# motor_driver_ver3_6.net
KiCad netlist of a schematic drawn in EAGLE
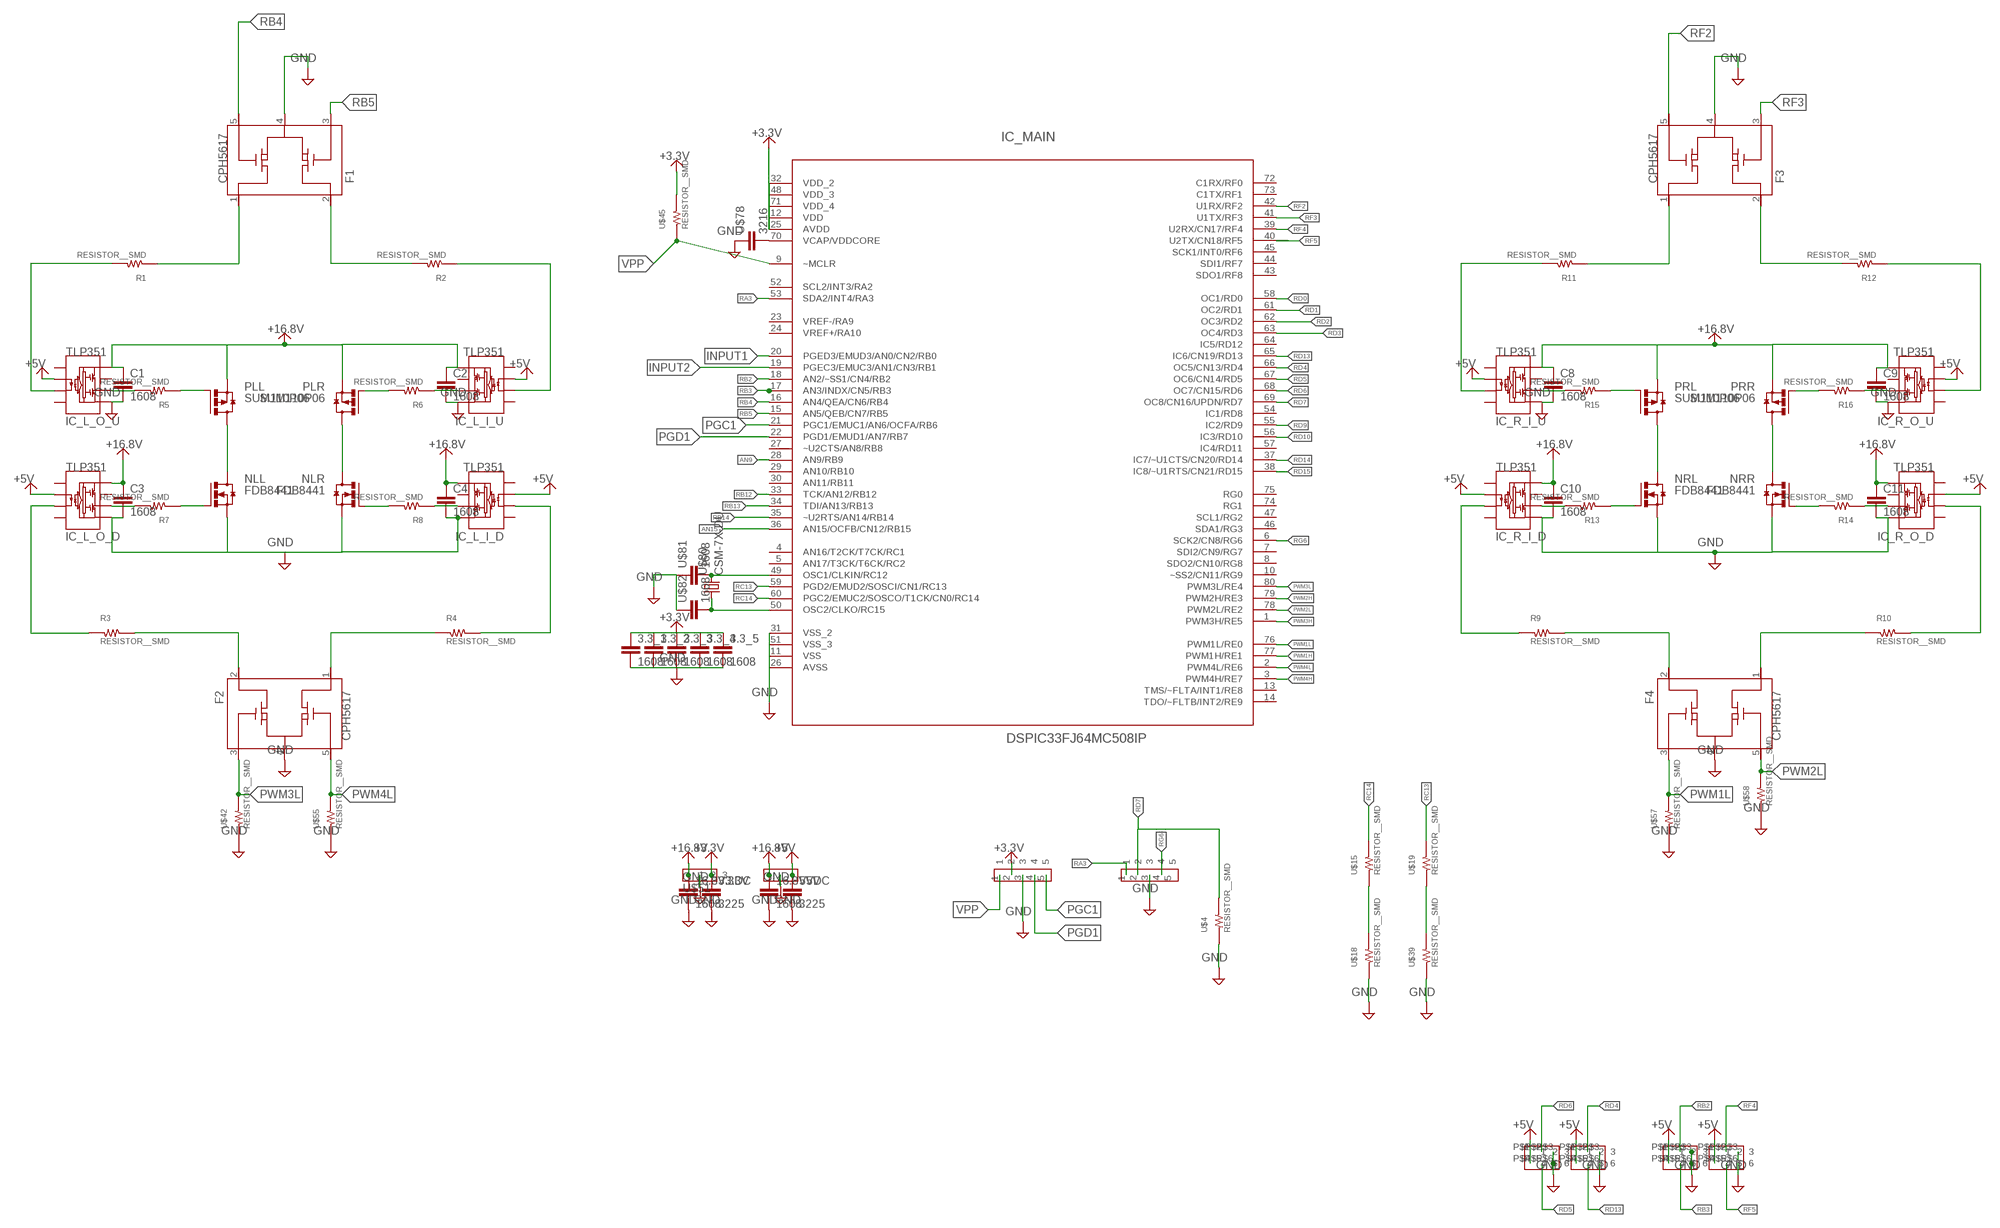
[diagram p0: schematic, sheet 1]

(export (version "E")
  (design (tool "Eeschema 10.0.6"))
  (components
    (comp (ref "3.3DC")
      (value "3225")
      (footprint "eagle-import:3225")
      (libsource (lib "eagle-import") (part "3225"))
    )
    (comp (ref "3.3_1")
      (value "1608")
      (footprint "eagle-import:1608")
      (libsource (lib "eagle-import") (part "1608"))
    )
    (comp (ref "3.3_2")
      (value "1608")
      (footprint "eagle-import:1608")
      (libsource (lib "eagle-import") (part "1608"))
    )
    (comp (ref "3.3_3")
      (value "1608")
      (footprint "eagle-import:1608")
      (libsource (lib "eagle-import") (part "1608"))
    )
    (comp (ref "3.3_4")
      (value "1608")
      (footprint "eagle-import:1608")
      (libsource (lib "eagle-import") (part "1608"))
    )
    (comp (ref "3.3_5")
      (value "1608")
      (footprint "eagle-import:1608")
      (libsource (lib "eagle-import") (part "1608"))
    )
    (comp (ref "5VDC")
      (value "3225")
      (footprint "eagle-import:3225")
      (libsource (lib "eagle-import") (part "3225"))
    )
    (comp (ref "16.8V3.3V")
      (value "1608")
      (footprint "eagle-import:1608")
      (libsource (lib "eagle-import") (part "1608"))
    )
    (comp (ref "16.8V5V")
      (value "1608")
      (footprint "eagle-import:1608")
      (libsource (lib "eagle-import") (part "1608"))
    )
    (comp (ref "C1")
      (value "1608")
      (footprint "eagle-import:1608")
      (libsource (lib "eagle-import") (part "1608"))
    )
    (comp (ref "C2")
      (value "1608")
      (footprint "eagle-import:1608")
      (libsource (lib "eagle-import") (part "1608"))
    )
    (comp (ref "C3")
      (value "1608")
      (footprint "eagle-import:1608")
      (libsource (lib "eagle-import") (part "1608"))
    )
    (comp (ref "C4")
      (value "1608")
      (footprint "eagle-import:1608")
      (libsource (lib "eagle-import") (part "1608"))
    )
    (comp (ref "C8")
      (value "1608")
      (footprint "eagle-import:1608")
      (libsource (lib "eagle-import") (part "1608"))
    )
    (comp (ref "C9")
      (value "1608")
      (footprint "eagle-import:1608")
      (libsource (lib "eagle-import") (part "1608"))
    )
    (comp (ref "C10")
      (value "1608")
      (footprint "eagle-import:1608")
      (libsource (lib "eagle-import") (part "1608"))
    )
    (comp (ref "C11")
      (value "1608")
      (footprint "eagle-import:1608")
      (libsource (lib "eagle-import") (part "1608"))
    )
    (comp (ref "F1")
      (value "CPH5617")
      (footprint "eagle-import:CHP-5")
      (libsource (lib "eagle-import") (part "CPH5617"))
    )
    (comp (ref "F2")
      (value "CPH5617")
      (footprint "eagle-import:CHP-5")
      (libsource (lib "eagle-import") (part "CPH5617"))
    )
    (comp (ref "F3")
      (value "CPH5617")
      (footprint "eagle-import:CHP-5")
      (libsource (lib "eagle-import") (part "CPH5617"))
    )
    (comp (ref "F4")
      (value "CPH5617")
      (footprint "eagle-import:CHP-5")
      (libsource (lib "eagle-import") (part "CPH5617"))
    )
    (comp (ref "IC_L_I_D")
      (value "TLP351")
      (footprint "eagle-import:DIL08")
      (libsource (lib "eagle-import") (part "TLP351"))
    )
    (comp (ref "IC_L_I_U")
      (value "TLP351")
      (footprint "eagle-import:DIL08")
      (libsource (lib "eagle-import") (part "TLP351"))
    )
    (comp (ref "IC_L_O_D")
      (value "TLP351")
      (footprint "eagle-import:DIL08")
      (libsource (lib "eagle-import") (part "TLP351"))
    )
    (comp (ref "IC_L_O_U")
      (value "TLP351")
      (footprint "eagle-import:DIL08")
      (libsource (lib "eagle-import") (part "TLP351"))
    )
    (comp (ref "IC_MAIN")
      (value "DSPIC33FJ64MC508IP")
      (footprint "eagle-import:QFP50P1400X1400X120-80N")
      (libsource (lib "eagle-import") (part "DSPIC33FJ64MC508IP"))
    )
    (comp (ref "IC_R_I_D")
      (value "TLP351")
      (footprint "eagle-import:DIL08")
      (libsource (lib "eagle-import") (part "TLP351"))
    )
    (comp (ref "IC_R_I_U")
      (value "TLP351")
      (footprint "eagle-import:DIL08")
      (libsource (lib "eagle-import") (part "TLP351"))
    )
    (comp (ref "IC_R_O_D")
      (value "TLP351")
      (footprint "eagle-import:DIL08")
      (libsource (lib "eagle-import") (part "TLP351"))
    )
    (comp (ref "IC_R_O_U")
      (value "TLP351")
      (footprint "eagle-import:DIL08")
      (libsource (lib "eagle-import") (part "TLP351"))
    )
    (comp (ref "NLL")
      (value "FDB8441")
      (footprint "eagle-import:TO-263")
      (libsource (lib "eagle-import") (part "FDB8441"))
    )
    (comp (ref "NLR")
      (value "FDB8441")
      (footprint "eagle-import:TO-263")
      (libsource (lib "eagle-import") (part "FDB8441"))
    )
    (comp (ref "NRL")
      (value "FDB8441")
      (footprint "eagle-import:TO-263")
      (libsource (lib "eagle-import") (part "FDB8441"))
    )
    (comp (ref "NRR")
      (value "FDB8441")
      (footprint "eagle-import:TO-263")
      (libsource (lib "eagle-import") (part "FDB8441"))
    )
    (comp (ref "PLL")
      (value "SUM110P06")
      (footprint "eagle-import:TO-263")
      (libsource (lib "eagle-import") (part "SUM110P06"))
    )
    (comp (ref "PLR")
      (value "SUM110P06")
      (footprint "eagle-import:TO-263")
      (libsource (lib "eagle-import") (part "SUM110P06"))
    )
    (comp (ref "PRL")
      (value "SUM110P06")
      (footprint "eagle-import:TO-263")
      (libsource (lib "eagle-import") (part "SUM110P06"))
    )
    (comp (ref "PRR")
      (value "SUM110P06")
      (footprint "eagle-import:TO-263")
      (libsource (lib "eagle-import") (part "SUM110P06"))
    )
    (comp (ref "R1")
      (value "RESISTOR__SMD")
      (footprint "eagle-import:1608")
      (libsource (lib "eagle-import") (part "RESISTOR__SMD"))
    )
    (comp (ref "R2")
      (value "RESISTOR__SMD")
      (footprint "eagle-import:1608")
      (libsource (lib "eagle-import") (part "RESISTOR__SMD"))
    )
    (comp (ref "R3")
      (value "RESISTOR__SMD")
      (footprint "eagle-import:1608")
      (libsource (lib "eagle-import") (part "RESISTOR__SMD"))
    )
    (comp (ref "R4")
      (value "RESISTOR__SMD")
      (footprint "eagle-import:1608")
      (libsource (lib "eagle-import") (part "RESISTOR__SMD"))
    )
    (comp (ref "R5")
      (value "RESISTOR__SMD")
      (footprint "eagle-import:1608")
      (libsource (lib "eagle-import") (part "RESISTOR__SMD"))
    )
    (comp (ref "R6")
      (value "RESISTOR__SMD")
      (footprint "eagle-import:1608")
      (libsource (lib "eagle-import") (part "RESISTOR__SMD"))
    )
    (comp (ref "R7")
      (value "RESISTOR__SMD")
      (footprint "eagle-import:1608")
      (libsource (lib "eagle-import") (part "RESISTOR__SMD"))
    )
    (comp (ref "R8")
      (value "RESISTOR__SMD")
      (footprint "eagle-import:1608")
      (libsource (lib "eagle-import") (part "RESISTOR__SMD"))
    )
    (comp (ref "R9")
      (value "RESISTOR__SMD")
      (footprint "eagle-import:1608")
      (libsource (lib "eagle-import") (part "RESISTOR__SMD"))
    )
    (comp (ref "R10")
      (value "RESISTOR__SMD")
      (footprint "eagle-import:1608")
      (libsource (lib "eagle-import") (part "RESISTOR__SMD"))
    )
    (comp (ref "R11")
      (value "RESISTOR__SMD")
      (footprint "eagle-import:1608")
      (libsource (lib "eagle-import") (part "RESISTOR__SMD"))
    )
    (comp (ref "R12")
      (value "RESISTOR__SMD")
      (footprint "eagle-import:1608")
      (libsource (lib "eagle-import") (part "RESISTOR__SMD"))
    )
    (comp (ref "R13")
      (value "RESISTOR__SMD")
      (footprint "eagle-import:1608")
      (libsource (lib "eagle-import") (part "RESISTOR__SMD"))
    )
    (comp (ref "R14")
      (value "RESISTOR__SMD")
      (footprint "eagle-import:1608")
      (libsource (lib "eagle-import") (part "RESISTOR__SMD"))
    )
    (comp (ref "R15")
      (value "RESISTOR__SMD")
      (footprint "eagle-import:1608")
      (libsource (lib "eagle-import") (part "RESISTOR__SMD"))
    )
    (comp (ref "R16")
      (value "RESISTOR__SMD")
      (footprint "eagle-import:1608")
      (libsource (lib "eagle-import") (part "RESISTOR__SMD"))
    )
    (comp (ref "U$1")
      (value "PIN_HEADER_5")
      (footprint "eagle-import:PIN_HEADER_5")
      (libsource (lib "eagle-import") (part "PIN_HEADER_5"))
    )
    (comp (ref "U$4")
      (value "RESISTOR__SMD")
      (footprint "eagle-import:1608")
      (libsource (lib "eagle-import") (part "RESISTOR__SMD"))
    )
    (comp (ref "U$5")
      (value "PIN_HEADER_32")
      (footprint "eagle-import:PIN_HEADER_3_2")
      (libsource (lib "eagle-import") (part "PIN_HEADER_32"))
    )
    (comp (ref "U$15")
      (value "RESISTOR__SMD")
      (footprint "eagle-import:1608")
      (libsource (lib "eagle-import") (part "RESISTOR__SMD"))
    )
    (comp (ref "U$18")
      (value "RESISTOR__SMD")
      (footprint "eagle-import:1608")
      (libsource (lib "eagle-import") (part "RESISTOR__SMD"))
    )
    (comp (ref "U$19")
      (value "RESISTOR__SMD")
      (footprint "eagle-import:1608")
      (libsource (lib "eagle-import") (part "RESISTOR__SMD"))
    )
    (comp (ref "U$20")
      (value "PIN_HEADER_32")
      (footprint "eagle-import:PIN_HEADER_3_2")
      (libsource (lib "eagle-import") (part "PIN_HEADER_32"))
    )
    (comp (ref "U$39")
      (value "RESISTOR__SMD")
      (footprint "eagle-import:1608")
      (libsource (lib "eagle-import") (part "RESISTOR__SMD"))
    )
    (comp (ref "U$42")
      (value "RESISTOR__SMD")
      (footprint "eagle-import:1608")
      (libsource (lib "eagle-import") (part "RESISTOR__SMD"))
    )
    (comp (ref "U$45")
      (value "RESISTOR__SMD")
      (footprint "eagle-import:1608")
      (libsource (lib "eagle-import") (part "RESISTOR__SMD"))
    )
    (comp (ref "U$47")
      (value "TA48M05")
      (footprint "eagle-import:ＨＳＩＰ３")
      (libsource (lib "eagle-import") (part "TA48M05"))
    )
    (comp (ref "U$51")
      (value "TA48M033")
      (footprint "eagle-import:ＨＳＩＰ３")
      (libsource (lib "eagle-import") (part "TA48M033"))
    )
    (comp (ref "U$55")
      (value "RESISTOR__SMD")
      (footprint "eagle-import:1608")
      (libsource (lib "eagle-import") (part "RESISTOR__SMD"))
    )
    (comp (ref "U$57")
      (value "RESISTOR__SMD")
      (footprint "eagle-import:1608")
      (libsource (lib "eagle-import") (part "RESISTOR__SMD"))
    )
    (comp (ref "U$58")
      (value "RESISTOR__SMD")
      (footprint "eagle-import:1608")
      (libsource (lib "eagle-import") (part "RESISTOR__SMD"))
    )
    (comp (ref "U$64")
      (value "PIN_HEADER_5")
      (footprint "eagle-import:PIN_HEADER_5")
      (libsource (lib "eagle-import") (part "PIN_HEADER_5"))
    )
    (comp (ref "U$66")
      (value "PIN_HEADER_32")
      (footprint "eagle-import:PIN_HEADER_3_2")
      (libsource (lib "eagle-import") (part "PIN_HEADER_32"))
    )
    (comp (ref "U$67")
      (value "PIN_HEADER_32")
      (footprint "eagle-import:PIN_HEADER_3_2")
      (libsource (lib "eagle-import") (part "PIN_HEADER_32"))
    )
    (comp (ref "U$78")
      (value "3216")
      (footprint "eagle-import:3216")
      (libsource (lib "eagle-import") (part "3216"))
    )
    (comp (ref "U$80")
      (value "CSM-7X-DU")
      (footprint "eagle-import:CSM-7X-DU")
      (libsource (lib "eagle-import") (part "CSM-7X-DU"))
    )
    (comp (ref "U$81")
      (value "1608")
      (footprint "eagle-import:1608")
      (libsource (lib "eagle-import") (part "1608"))
    )
    (comp (ref "U$82")
      (value "1608")
      (footprint "eagle-import:1608")
      (libsource (lib "eagle-import") (part "1608"))
    )
  )
  (nets
    (net (code "1") (name "+3.3V") (class "Default")
      (node (ref "3.3DC") (pin "P$1") (pinfunction "1_P$1") (pintype "passive"))
      (node (ref "3.3_1") (pin "P$1") (pinfunction "1_P$1") (pintype "passive"))
      (node (ref "3.3_2") (pin "P$1") (pinfunction "1_P$1") (pintype "passive"))
      (node (ref "3.3_3") (pin "P$1") (pinfunction "1_P$1") (pintype "passive"))
      (node (ref "3.3_4") (pin "P$1") (pinfunction "1_P$1") (pintype "passive"))
      (node (ref "3.3_5") (pin "P$1") (pinfunction "1_P$1") (pintype "passive"))
      (node (ref "IC_MAIN") (pin "12") (pinfunction "VDD_12") (pintype "power_in"))
      (node (ref "IC_MAIN") (pin "25") (pinfunction "AVDD_25") (pintype "power_in"))
      (node (ref "IC_MAIN") (pin "32") (pinfunction "VDD_2_32") (pintype "power_in"))
      (node (ref "IC_MAIN") (pin "48") (pinfunction "VDD_3_48") (pintype "power_in"))
      (node (ref "IC_MAIN") (pin "71") (pinfunction "VDD_4_71") (pintype "power_in"))
      (node (ref "U$1") (pin "2") (pinfunction "2_2") (pintype "bidirectional"))
      (node (ref "U$45") (pin "2") (pinfunction "P$2_2") (pintype "passive"))
      (node (ref "U$51") (pin "3") (pinfunction "3_3") (pintype "bidirectional"))
    )
    (net (code "2") (name "+5V") (class "Default")
      (node (ref "5VDC") (pin "P$1") (pinfunction "1_P$1") (pintype "passive"))
      (node (ref "IC_L_I_D") (pin "2") (pinfunction "LED+_2") (pintype "bidirectional"))
      (node (ref "IC_L_I_U") (pin "2") (pinfunction "LED+_2") (pintype "bidirectional"))
      (node (ref "IC_L_O_D") (pin "2") (pinfunction "LED+_2") (pintype "bidirectional"))
      (node (ref "IC_L_O_U") (pin "2") (pinfunction "LED+_2") (pintype "bidirectional"))
      (node (ref "IC_R_I_D") (pin "2") (pinfunction "LED+_2") (pintype "bidirectional"))
      (node (ref "IC_R_I_U") (pin "2") (pinfunction "LED+_2") (pintype "bidirectional"))
      (node (ref "IC_R_O_D") (pin "2") (pinfunction "LED+_2") (pintype "bidirectional"))
      (node (ref "IC_R_O_U") (pin "2") (pinfunction "LED+_2") (pintype "bidirectional"))
      (node (ref "U$20") (pin "P$1") (pinfunction "1_P$1") (pintype "bidirectional"))
      (node (ref "U$20") (pin "P$4") (pinfunction "4_P$4") (pintype "bidirectional"))
      (node (ref "U$47") (pin "3") (pinfunction "OUT_3") (pintype "bidirectional"))
      (node (ref "U$5") (pin "P$1") (pinfunction "1_P$1") (pintype "bidirectional"))
      (node (ref "U$5") (pin "P$4") (pinfunction "4_P$4") (pintype "bidirectional"))
      (node (ref "U$66") (pin "P$1") (pinfunction "1_P$1") (pintype "bidirectional"))
      (node (ref "U$66") (pin "P$4") (pinfunction "4_P$4") (pintype "bidirectional"))
      (node (ref "U$67") (pin "P$1") (pinfunction "1_P$1") (pintype "bidirectional"))
      (node (ref "U$67") (pin "P$4") (pinfunction "4_P$4") (pintype "bidirectional"))
    )
    (net (code "3") (name "+16.8V") (class "Default")
      (node (ref "16.8V3.3V") (pin "P$1") (pinfunction "1_P$1") (pintype "passive"))
      (node (ref "16.8V5V") (pin "P$1") (pinfunction "1_P$1") (pintype "passive"))
      (node (ref "C1") (pin "P$1") (pinfunction "1_P$1") (pintype "passive"))
      (node (ref "C10") (pin "P$1") (pinfunction "1_P$1") (pintype "passive"))
      (node (ref "C11") (pin "P$1") (pinfunction "1_P$1") (pintype "passive"))
      (node (ref "C2") (pin "P$1") (pinfunction "1_P$1") (pintype "passive"))
      (node (ref "C3") (pin "P$1") (pinfunction "1_P$1") (pintype "passive"))
      (node (ref "C4") (pin "P$1") (pinfunction "1_P$1") (pintype "passive"))
      (node (ref "C8") (pin "P$1") (pinfunction "1_P$1") (pintype "passive"))
      (node (ref "C9") (pin "P$1") (pinfunction "1_P$1") (pintype "passive"))
      (node (ref "IC_L_I_D") (pin "8") (pinfunction "VDD_8") (pintype "bidirectional"))
      (node (ref "IC_L_I_U") (pin "8") (pinfunction "VDD_8") (pintype "bidirectional"))
      (node (ref "IC_L_O_D") (pin "8") (pinfunction "VDD_8") (pintype "bidirectional"))
      (node (ref "IC_L_O_U") (pin "8") (pinfunction "VDD_8") (pintype "bidirectional"))
      (node (ref "IC_R_I_D") (pin "8") (pinfunction "VDD_8") (pintype "bidirectional"))
      (node (ref "IC_R_I_U") (pin "8") (pinfunction "VDD_8") (pintype "bidirectional"))
      (node (ref "IC_R_O_D") (pin "8") (pinfunction "VDD_8") (pintype "bidirectional"))
      (node (ref "IC_R_O_U") (pin "8") (pinfunction "VDD_8") (pintype "bidirectional"))
      (node (ref "PLL") (pin "2") (pinfunction "S_2") (pintype "passive"))
      (node (ref "PLR") (pin "2") (pinfunction "S_2") (pintype "passive"))
      (node (ref "PRL") (pin "2") (pinfunction "S_2") (pintype "passive"))
      (node (ref "PRR") (pin "2") (pinfunction "S_2") (pintype "passive"))
      (node (ref "U$47") (pin "1") (pinfunction "IN_1") (pintype "bidirectional"))
      (node (ref "U$51") (pin "1") (pinfunction "1_1") (pintype "bidirectional"))
    )
    (net (code "4") (name "AN9") (class "Default")
      (node (ref "IC_MAIN") (pin "28") (pinfunction "AN9/RB9_28") (pintype "bidirectional"))
    )
    (net (code "5") (name "AN15") (class "Default")
      (node (ref "IC_MAIN") (pin "36") (pinfunction "AN15/OCFB/CN12/RB15_36") (pintype "bidirectional"))
    )
    (net (code "6") (name "GND") (class "Default")
      (node (ref "16.8V3.3V") (pin "P$2") (pinfunction "2_P$2") (pintype "passive"))
      (node (ref "16.8V5V") (pin "P$2") (pinfunction "2_P$2") (pintype "passive"))
      (node (ref "3.3DC") (pin "P$2") (pinfunction "2_P$2") (pintype "passive"))
      (node (ref "3.3_1") (pin "P$2") (pinfunction "2_P$2") (pintype "passive"))
      (node (ref "3.3_2") (pin "P$2") (pinfunction "2_P$2") (pintype "passive"))
      (node (ref "3.3_3") (pin "P$2") (pinfunction "2_P$2") (pintype "passive"))
      (node (ref "3.3_4") (pin "P$2") (pinfunction "2_P$2") (pintype "passive"))
      (node (ref "3.3_5") (pin "P$2") (pinfunction "2_P$2") (pintype "passive"))
      (node (ref "5VDC") (pin "P$2") (pinfunction "2_P$2") (pintype "passive"))
      (node (ref "C1") (pin "P$2") (pinfunction "2_P$2") (pintype "passive"))
      (node (ref "C10") (pin "P$2") (pinfunction "2_P$2") (pintype "passive"))
      (node (ref "C11") (pin "P$2") (pinfunction "2_P$2") (pintype "passive"))
      (node (ref "C2") (pin "P$2") (pinfunction "2_P$2") (pintype "passive"))
      (node (ref "C3") (pin "P$2") (pinfunction "2_P$2") (pintype "passive"))
      (node (ref "C4") (pin "P$2") (pinfunction "2_P$2") (pintype "passive"))
      (node (ref "C8") (pin "P$2") (pinfunction "2_P$2") (pintype "passive"))
      (node (ref "C9") (pin "P$2") (pinfunction "2_P$2") (pintype "passive"))
      (node (ref "F1") (pin "4") (pinfunction "S_4") (pintype "bidirectional"))
      (node (ref "F2") (pin "4") (pinfunction "S_4") (pintype "bidirectional"))
      (node (ref "F3") (pin "4") (pinfunction "S_4") (pintype "bidirectional"))
      (node (ref "F4") (pin "4") (pinfunction "S_4") (pintype "bidirectional"))
      (node (ref "IC_L_I_D") (pin "5") (pinfunction "GND_5") (pintype "bidirectional"))
      (node (ref "IC_L_I_U") (pin "5") (pinfunction "GND_5") (pintype "bidirectional"))
      (node (ref "IC_L_O_D") (pin "5") (pinfunction "GND_5") (pintype "bidirectional"))
      (node (ref "IC_L_O_U") (pin "5") (pinfunction "GND_5") (pintype "bidirectional"))
      (node (ref "IC_MAIN") (pin "11") (pinfunction "VSS_11") (pintype "power_in"))
      (node (ref "IC_MAIN") (pin "26") (pinfunction "AVSS_26") (pintype "power_in"))
      (node (ref "IC_MAIN") (pin "31") (pinfunction "VSS_2_31") (pintype "power_in"))
      (node (ref "IC_MAIN") (pin "51") (pinfunction "VSS_3_51") (pintype "power_in"))
      (node (ref "IC_R_I_D") (pin "5") (pinfunction "GND_5") (pintype "bidirectional"))
      (node (ref "IC_R_I_U") (pin "5") (pinfunction "GND_5") (pintype "bidirectional"))
      (node (ref "IC_R_O_D") (pin "5") (pinfunction "GND_5") (pintype "bidirectional"))
      (node (ref "IC_R_O_U") (pin "5") (pinfunction "GND_5") (pintype "bidirectional"))
      (node (ref "NLL") (pin "2") (pinfunction "S_2") (pintype "passive"))
      (node (ref "NLR") (pin "2") (pinfunction "S_2") (pintype "passive"))
      (node (ref "NRL") (pin "2") (pinfunction "S_2") (pintype "passive"))
      (node (ref "NRR") (pin "2") (pinfunction "S_2") (pintype "passive"))
      (node (ref "U$1") (pin "3") (pinfunction "3_3") (pintype "bidirectional"))
      (node (ref "U$18") (pin "1") (pinfunction "P$1_1") (pintype "passive"))
      (node (ref "U$20") (pin "P$3") (pinfunction "3_P$3") (pintype "bidirectional"))
      (node (ref "U$20") (pin "P$6") (pinfunction "6_P$6") (pintype "bidirectional"))
      (node (ref "U$39") (pin "1") (pinfunction "P$1_1") (pintype "passive"))
      (node (ref "U$4") (pin "1") (pinfunction "P$1_1") (pintype "passive"))
      (node (ref "U$42") (pin "1") (pinfunction "P$1_1") (pintype "passive"))
      (node (ref "U$47") (pin "2") (pinfunction "GND_2") (pintype "bidirectional"))
      (node (ref "U$5") (pin "P$3") (pinfunction "3_P$3") (pintype "bidirectional"))
      (node (ref "U$5") (pin "P$6") (pinfunction "6_P$6") (pintype "bidirectional"))
      (node (ref "U$51") (pin "2") (pinfunction "2_2") (pintype "bidirectional"))
      (node (ref "U$55") (pin "1") (pinfunction "P$1_1") (pintype "passive"))
      (node (ref "U$57") (pin "1") (pinfunction "P$1_1") (pintype "passive"))
      (node (ref "U$58") (pin "1") (pinfunction "P$1_1") (pintype "passive"))
      (node (ref "U$64") (pin "3") (pinfunction "3_3") (pintype "bidirectional"))
      (node (ref "U$66") (pin "P$3") (pinfunction "3_P$3") (pintype "bidirectional"))
      (node (ref "U$66") (pin "P$6") (pinfunction "6_P$6") (pintype "bidirectional"))
      (node (ref "U$67") (pin "P$3") (pinfunction "3_P$3") (pintype "bidirectional"))
      (node (ref "U$67") (pin "P$6") (pinfunction "6_P$6") (pintype "bidirectional"))
      (node (ref "U$78") (pin "P$1") (pinfunction "1_P$1") (pintype "passive"))
      (node (ref "U$81") (pin "P$1") (pinfunction "1_P$1") (pintype "passive"))
      (node (ref "U$82") (pin "P$1") (pinfunction "1_P$1") (pintype "passive"))
    )
    (net (code "7") (name "INPUT1") (class "Default")
      (node (ref "IC_MAIN") (pin "20") (pinfunction "PGED3/EMUD3/AN0/CN2/RB0_20") (pintype "bidirectional"))
    )
    (net (code "8") (name "INPUT2") (class "Default")
      (node (ref "IC_MAIN") (pin "19") (pinfunction "PGEC3/EMUC3/AN1/CN3/RB1_19") (pintype "bidirectional"))
    )
    (net (code "9") (name "Net-(F1-D1)") (class "Default")
      (node (ref "F1") (pin "1") (pinfunction "D1_1") (pintype "bidirectional"))
      (node (ref "R1") (pin "1") (pinfunction "P$1_1") (pintype "passive"))
    )
    (net (code "10") (name "Net-(F1-D2)") (class "Default")
      (node (ref "F1") (pin "2") (pinfunction "D2_2") (pintype "bidirectional"))
      (node (ref "R2") (pin "2") (pinfunction "P$2_2") (pintype "passive"))
    )
    (net (code "11") (name "Net-(F2-D1)") (class "Default")
      (node (ref "F2") (pin "1") (pinfunction "D1_1") (pintype "bidirectional"))
      (node (ref "R4") (pin "1") (pinfunction "P$1_1") (pintype "passive"))
    )
    (net (code "12") (name "Net-(F2-D2)") (class "Default")
      (node (ref "F2") (pin "2") (pinfunction "D2_2") (pintype "bidirectional"))
      (node (ref "R3") (pin "2") (pinfunction "P$2_2") (pintype "passive"))
    )
    (net (code "13") (name "Net-(F3-D1)") (class "Default")
      (node (ref "F3") (pin "1") (pinfunction "D1_1") (pintype "bidirectional"))
      (node (ref "R11") (pin "1") (pinfunction "P$1_1") (pintype "passive"))
    )
    (net (code "14") (name "Net-(F3-D2)") (class "Default")
      (node (ref "F3") (pin "2") (pinfunction "D2_2") (pintype "bidirectional"))
      (node (ref "R12") (pin "2") (pinfunction "P$2_2") (pintype "passive"))
    )
    (net (code "15") (name "Net-(F4-D1)") (class "Default")
      (node (ref "F4") (pin "1") (pinfunction "D1_1") (pintype "bidirectional"))
      (node (ref "R10") (pin "1") (pinfunction "P$1_1") (pintype "passive"))
    )
    (net (code "16") (name "Net-(F4-D2)") (class "Default")
      (node (ref "F4") (pin "2") (pinfunction "D2_2") (pintype "bidirectional"))
      (node (ref "R9") (pin "2") (pinfunction "P$2_2") (pintype "passive"))
    )
    (net (code "17") (name "Net-(IC_L_I_D-LED-)") (class "Default")
      (node (ref "IC_L_I_D") (pin "3") (pinfunction "LED-_3") (pintype "bidirectional"))
      (node (ref "R4") (pin "2") (pinfunction "P$2_2") (pintype "passive"))
    )
    (net (code "18") (name "Net-(IC_L_I_D-OUT)") (class "Default")
      (node (ref "IC_L_I_D") (pin "6") (pinfunction "OUT_6") (pintype "output"))
      (node (ref "R8") (pin "1") (pinfunction "P$1_1") (pintype "passive"))
    )
    (net (code "19") (name "Net-(IC_L_I_U-LED-)") (class "Default")
      (node (ref "IC_L_I_U") (pin "3") (pinfunction "LED-_3") (pintype "bidirectional"))
      (node (ref "R2") (pin "1") (pinfunction "P$1_1") (pintype "passive"))
    )
    (net (code "20") (name "Net-(IC_L_I_U-OUT)") (class "Default")
      (node (ref "IC_L_I_U") (pin "6") (pinfunction "OUT_6") (pintype "output"))
      (node (ref "R6") (pin "1") (pinfunction "P$1_1") (pintype "passive"))
    )
    (net (code "21") (name "Net-(IC_L_O_D-LED-)") (class "Default")
      (node (ref "IC_L_O_D") (pin "3") (pinfunction "LED-_3") (pintype "bidirectional"))
      (node (ref "R3") (pin "1") (pinfunction "P$1_1") (pintype "passive"))
    )
    (net (code "22") (name "Net-(IC_L_O_D-OUT)") (class "Default")
      (node (ref "IC_L_O_D") (pin "6") (pinfunction "OUT_6") (pintype "output"))
      (node (ref "R7") (pin "2") (pinfunction "P$2_2") (pintype "passive"))
    )
    (net (code "23") (name "Net-(IC_L_O_U-LED-)") (class "Default")
      (node (ref "IC_L_O_U") (pin "3") (pinfunction "LED-_3") (pintype "bidirectional"))
      (node (ref "R1") (pin "2") (pinfunction "P$2_2") (pintype "passive"))
    )
    (net (code "24") (name "Net-(IC_L_O_U-OUT)") (class "Default")
      (node (ref "IC_L_O_U") (pin "6") (pinfunction "OUT_6") (pintype "output"))
      (node (ref "R5") (pin "2") (pinfunction "P$2_2") (pintype "passive"))
    )
    (net (code "25") (name "Net-(IC_MAIN-OSC1{slash}CLKIN{slash}RC12)") (class "Default")
      (node (ref "IC_MAIN") (pin "49") (pinfunction "OSC1/CLKIN/RC12_49") (pintype "bidirectional"))
      (node (ref "U$80") (pin "2") (pinfunction "2_2") (pintype "passive"))
      (node (ref "U$81") (pin "P$2") (pinfunction "2_P$2") (pintype "passive"))
    )
    (net (code "26") (name "Net-(IC_MAIN-OSC2{slash}CLKO{slash}RC15)") (class "Default")
      (node (ref "IC_MAIN") (pin "50") (pinfunction "OSC2/CLKO/RC15_50") (pintype "bidirectional"))
      (node (ref "U$80") (pin "1") (pinfunction "1_1") (pintype "passive"))
      (node (ref "U$82") (pin "P$2") (pinfunction "2_P$2") (pintype "passive"))
    )
    (net (code "27") (name "Net-(IC_MAIN-VCAP{slash}VDDCORE)") (class "Default")
      (node (ref "IC_MAIN") (pin "70") (pinfunction "VCAP/VDDCORE_70") (pintype "power_in"))
      (node (ref "U$78") (pin "P$2") (pinfunction "2_P$2") (pintype "passive"))
    )
    (net (code "28") (name "Net-(IC_R_I_D-LED-)") (class "Default")
      (node (ref "IC_R_I_D") (pin "3") (pinfunction "LED-_3") (pintype "bidirectional"))
      (node (ref "R9") (pin "1") (pinfunction "P$1_1") (pintype "passive"))
    )
    (net (code "29") (name "Net-(IC_R_I_D-OUT)") (class "Default")
      (node (ref "IC_R_I_D") (pin "6") (pinfunction "OUT_6") (pintype "output"))
      (node (ref "R13") (pin "2") (pinfunction "P$2_2") (pintype "passive"))
    )
    (net (code "30") (name "Net-(IC_R_I_U-LED-)") (class "Default")
      (node (ref "IC_R_I_U") (pin "3") (pinfunction "LED-_3") (pintype "bidirectional"))
      (node (ref "R11") (pin "2") (pinfunction "P$2_2") (pintype "passive"))
    )
    (net (code "31") (name "Net-(IC_R_I_U-OUT)") (class "Default")
      (node (ref "IC_R_I_U") (pin "6") (pinfunction "OUT_6") (pintype "output"))
      (node (ref "R15") (pin "2") (pinfunction "P$2_2") (pintype "passive"))
    )
    (net (code "32") (name "Net-(IC_R_O_D-LED-)") (class "Default")
      (node (ref "IC_R_O_D") (pin "3") (pinfunction "LED-_3") (pintype "bidirectional"))
      (node (ref "R10") (pin "2") (pinfunction "P$2_2") (pintype "passive"))
    )
    (net (code "33") (name "Net-(IC_R_O_D-OUT)") (class "Default")
      (node (ref "IC_R_O_D") (pin "6") (pinfunction "OUT_6") (pintype "output"))
      (node (ref "R14") (pin "1") (pinfunction "P$1_1") (pintype "passive"))
    )
    (net (code "34") (name "Net-(IC_R_O_U-LED-)") (class "Default")
      (node (ref "IC_R_O_U") (pin "3") (pinfunction "LED-_3") (pintype "bidirectional"))
      (node (ref "R12") (pin "1") (pinfunction "P$1_1") (pintype "passive"))
    )
    (net (code "35") (name "Net-(IC_R_O_U-OUT)") (class "Default")
      (node (ref "IC_R_O_U") (pin "6") (pinfunction "OUT_6") (pintype "output"))
      (node (ref "R16") (pin "1") (pinfunction "P$1_1") (pintype "passive"))
    )
    (net (code "36") (name "Net-(NLL-D)") (class "Default")
      (node (ref "NLL") (pin "3") (pinfunction "D_3") (pintype "passive"))
      (node (ref "PLL") (pin "3") (pinfunction "D_3") (pintype "passive"))
    )
    (net (code "37") (name "Net-(NLL-G)") (class "Default")
      (node (ref "NLL") (pin "1") (pinfunction "G_1") (pintype "passive"))
      (node (ref "R7") (pin "1") (pinfunction "P$1_1") (pintype "passive"))
    )
    (net (code "38") (name "Net-(NLR-D)") (class "Default")
      (node (ref "NLR") (pin "3") (pinfunction "D_3") (pintype "passive"))
      (node (ref "PLR") (pin "3") (pinfunction "D_3") (pintype "passive"))
    )
    (net (code "39") (name "Net-(NLR-G)") (class "Default")
      (node (ref "NLR") (pin "1") (pinfunction "G_1") (pintype "passive"))
      (node (ref "R8") (pin "2") (pinfunction "P$2_2") (pintype "passive"))
    )
    (net (code "40") (name "Net-(NRL-D)") (class "Default")
      (node (ref "NRL") (pin "3") (pinfunction "D_3") (pintype "passive"))
      (node (ref "PRL") (pin "3") (pinfunction "D_3") (pintype "passive"))
    )
    (net (code "41") (name "Net-(NRL-G)") (class "Default")
      (node (ref "NRL") (pin "1") (pinfunction "G_1") (pintype "passive"))
      (node (ref "R13") (pin "1") (pinfunction "P$1_1") (pintype "passive"))
    )
    (net (code "42") (name "Net-(NRR-D)") (class "Default")
      (node (ref "NRR") (pin "3") (pinfunction "D_3") (pintype "passive"))
      (node (ref "PRR") (pin "3") (pinfunction "D_3") (pintype "passive"))
    )
    (net (code "43") (name "Net-(NRR-G)") (class "Default")
      (node (ref "NRR") (pin "1") (pinfunction "G_1") (pintype "passive"))
      (node (ref "R14") (pin "2") (pinfunction "P$2_2") (pintype "passive"))
    )
    (net (code "44") (name "Net-(PLL-G)") (class "Default")
      (node (ref "PLL") (pin "1") (pinfunction "G_1") (pintype "passive"))
      (node (ref "R5") (pin "1") (pinfunction "P$1_1") (pintype "passive"))
    )
    (net (code "45") (name "Net-(PLR-G)") (class "Default")
      (node (ref "PLR") (pin "1") (pinfunction "G_1") (pintype "passive"))
      (node (ref "R6") (pin "2") (pinfunction "P$2_2") (pintype "passive"))
    )
    (net (code "46") (name "Net-(PRL-G)") (class "Default")
      (node (ref "PRL") (pin "1") (pinfunction "G_1") (pintype "passive"))
      (node (ref "R15") (pin "1") (pinfunction "P$1_1") (pintype "passive"))
    )
    (net (code "47") (name "Net-(PRR-G)") (class "Default")
      (node (ref "PRR") (pin "1") (pinfunction "G_1") (pintype "passive"))
      (node (ref "R16") (pin "2") (pinfunction "P$2_2") (pintype "passive"))
    )
    (net (code "48") (name "Net-(U$15-P$1)") (class "Default")
      (node (ref "U$15") (pin "1") (pinfunction "P$1_1") (pintype "passive"))
      (node (ref "U$18") (pin "2") (pinfunction "P$2_2") (pintype "passive"))
    )
    (net (code "49") (name "Net-(U$19-P$1)") (class "Default")
      (node (ref "U$19") (pin "1") (pinfunction "P$1_1") (pintype "passive"))
      (node (ref "U$39") (pin "2") (pinfunction "P$2_2") (pintype "passive"))
    )
    (net (code "50") (name "PGC1") (class "Default")
      (node (ref "IC_MAIN") (pin "21") (pinfunction "PGC1/EMUC1/AN6/OCFA/RB6_21") (pintype "bidirectional"))
      (node (ref "U$1") (pin "5") (pinfunction "5_5") (pintype "bidirectional"))
    )
    (net (code "51") (name "PGD1") (class "Default")
      (node (ref "IC_MAIN") (pin "22") (pinfunction "PGD1/EMUD1/AN7/RB7_22") (pintype "bidirectional"))
      (node (ref "U$1") (pin "4") (pinfunction "4_4") (pintype "bidirectional"))
    )
    (net (code "52") (name "PWM1H") (class "Default")
      (node (ref "IC_MAIN") (pin "77") (pinfunction "PWM1H/RE1_77") (pintype "bidirectional"))
    )
    (net (code "53") (name "PWM1L") (class "Default")
      (node (ref "F4") (pin "3") (pinfunction "G2_3") (pintype "bidirectional"))
      (node (ref "IC_MAIN") (pin "76") (pinfunction "PWM1L/RE0_76") (pintype "bidirectional"))
      (node (ref "U$57") (pin "2") (pinfunction "P$2_2") (pintype "passive"))
    )
    (net (code "54") (name "PWM2H") (class "Default")
      (node (ref "IC_MAIN") (pin "79") (pinfunction "PWM2H/RE3_79") (pintype "bidirectional"))
    )
    (net (code "55") (name "PWM2L") (class "Default")
      (node (ref "F4") (pin "5") (pinfunction "G1_5") (pintype "bidirectional"))
      (node (ref "IC_MAIN") (pin "78") (pinfunction "PWM2L/RE2_78") (pintype "bidirectional"))
      (node (ref "U$58") (pin "2") (pinfunction "P$2_2") (pintype "passive"))
    )
    (net (code "56") (name "PWM3H") (class "Default")
      (node (ref "IC_MAIN") (pin "1") (pinfunction "PWM3H/RE5_1") (pintype "bidirectional"))
    )
    (net (code "57") (name "PWM3L") (class "Default")
      (node (ref "F2") (pin "3") (pinfunction "G2_3") (pintype "bidirectional"))
      (node (ref "IC_MAIN") (pin "80") (pinfunction "PWM3L/RE4_80") (pintype "bidirectional"))
      (node (ref "U$42") (pin "2") (pinfunction "P$2_2") (pintype "passive"))
    )
    (net (code "58") (name "PWM4H") (class "Default")
      (node (ref "IC_MAIN") (pin "3") (pinfunction "PWM4H/RE7_3") (pintype "bidirectional"))
    )
    (net (code "59") (name "PWM4L") (class "Default")
      (node (ref "F2") (pin "5") (pinfunction "G1_5") (pintype "bidirectional"))
      (node (ref "IC_MAIN") (pin "2") (pinfunction "PWM4L/RE6_2") (pintype "bidirectional"))
      (node (ref "U$55") (pin "2") (pinfunction "P$2_2") (pintype "passive"))
    )
    (net (code "60") (name "RA3") (class "Default")
      (node (ref "IC_MAIN") (pin "53") (pinfunction "SDA2/INT4/RA3_53") (pintype "bidirectional"))
      (node (ref "U$64") (pin "1") (pinfunction "1_1") (pintype "bidirectional"))
    )
    (net (code "61") (name "RB2") (class "Default")
      (node (ref "IC_MAIN") (pin "18") (pinfunction "AN2/~{SS1/CN4/RB2}_18") (pintype "bidirectional"))
      (node (ref "U$5") (pin "P$2") (pinfunction "2_P$2") (pintype "bidirectional"))
    )
    (net (code "62") (name "RB3") (class "Default")
      (node (ref "IC_MAIN") (pin "17") (pinfunction "AN3/INDX/CN5/RB3_17") (pintype "bidirectional"))
      (node (ref "U$5") (pin "P$5") (pinfunction "5_P$5") (pintype "bidirectional"))
    )
    (net (code "63") (name "RB4") (class "Default")
      (node (ref "F1") (pin "5") (pinfunction "G1_5") (pintype "bidirectional"))
      (node (ref "IC_MAIN") (pin "16") (pinfunction "AN4/QEA/CN6/RB4_16") (pintype "bidirectional"))
    )
    (net (code "64") (name "RB5") (class "Default")
      (node (ref "F1") (pin "3") (pinfunction "G2_3") (pintype "bidirectional"))
      (node (ref "IC_MAIN") (pin "15") (pinfunction "AN5/QEB/CN7/RB5_15") (pintype "bidirectional"))
    )
    (net (code "65") (name "RB12") (class "Default")
      (node (ref "IC_MAIN") (pin "33") (pinfunction "TCK/AN12/RB12_33") (pintype "bidirectional"))
    )
    (net (code "66") (name "RB13") (class "Default")
      (node (ref "IC_MAIN") (pin "34") (pinfunction "TDI/AN13/RB13_34") (pintype "bidirectional"))
    )
    (net (code "67") (name "RB14") (class "Default")
      (node (ref "IC_MAIN") (pin "35") (pinfunction "~{U2RTS/AN14/RB14}_35") (pintype "bidirectional"))
    )
    (net (code "68") (name "RC13") (class "Default")
      (node (ref "IC_MAIN") (pin "59") (pinfunction "PGD2/EMUD2/SOSCI/CN1/RC13_59") (pintype "bidirectional"))
      (node (ref "U$19") (pin "2") (pinfunction "P$2_2") (pintype "passive"))
    )
    (net (code "69") (name "RC14") (class "Default")
      (node (ref "IC_MAIN") (pin "60") (pinfunction "PGC2/EMUC2/SOSCO/T1CK/CN0/RC14_60") (pintype "bidirectional"))
      (node (ref "U$15") (pin "2") (pinfunction "P$2_2") (pintype "passive"))
    )
    (net (code "70") (name "RD0") (class "Default")
      (node (ref "IC_MAIN") (pin "58") (pinfunction "OC1/RD0_58") (pintype "bidirectional"))
    )
    (net (code "71") (name "RD1") (class "Default")
      (node (ref "IC_MAIN") (pin "61") (pinfunction "OC2/RD1_61") (pintype "bidirectional"))
    )
    (net (code "72") (name "RD2") (class "Default")
      (node (ref "IC_MAIN") (pin "62") (pinfunction "OC3/RD2_62") (pintype "bidirectional"))
    )
    (net (code "73") (name "RD3") (class "Default")
      (node (ref "IC_MAIN") (pin "63") (pinfunction "OC4/RD3_63") (pintype "bidirectional"))
    )
    (net (code "74") (name "RD4") (class "Default")
      (node (ref "IC_MAIN") (pin "66") (pinfunction "OC5/CN13/RD4_66") (pintype "bidirectional"))
      (node (ref "U$67") (pin "P$2") (pinfunction "2_P$2") (pintype "bidirectional"))
    )
    (net (code "75") (name "RD5") (class "Default")
      (node (ref "IC_MAIN") (pin "67") (pinfunction "OC6/CN14/RD5_67") (pintype "bidirectional"))
      (node (ref "U$66") (pin "P$5") (pinfunction "5_P$5") (pintype "bidirectional"))
    )
    (net (code "76") (name "RD6") (class "Default")
      (node (ref "IC_MAIN") (pin "68") (pinfunction "OC7/CN15/RD6_68") (pintype "bidirectional"))
      (node (ref "U$66") (pin "P$2") (pinfunction "2_P$2") (pintype "bidirectional"))
    )
    (net (code "77") (name "RD7") (class "Default")
      (node (ref "IC_MAIN") (pin "69") (pinfunction "OC8/CN16/UPDN/RD7_69") (pintype "bidirectional"))
      (node (ref "U$4") (pin "2") (pinfunction "P$2_2") (pintype "passive"))
      (node (ref "U$64") (pin "2") (pinfunction "2_2") (pintype "bidirectional"))
    )
    (net (code "78") (name "RD9") (class "Default")
      (node (ref "IC_MAIN") (pin "55") (pinfunction "IC2/RD9_55") (pintype "bidirectional"))
    )
    (net (code "79") (name "RD10") (class "Default")
      (node (ref "IC_MAIN") (pin "56") (pinfunction "IC3/RD10_56") (pintype "bidirectional"))
    )
    (net (code "80") (name "RD13") (class "Default")
      (node (ref "IC_MAIN") (pin "65") (pinfunction "IC6/CN19/RD13_65") (pintype "bidirectional"))
      (node (ref "U$67") (pin "P$5") (pinfunction "5_P$5") (pintype "bidirectional"))
    )
    (net (code "81") (name "RD14") (class "Default")
      (node (ref "IC_MAIN") (pin "37") (pinfunction "IC7/~{U1CTS/CN20/RD14}_37") (pintype "bidirectional"))
    )
    (net (code "82") (name "RD15") (class "Default")
      (node (ref "IC_MAIN") (pin "38") (pinfunction "IC8/~{U1RTS/CN21/RD15}_38") (pintype "bidirectional"))
    )
    (net (code "83") (name "RF2") (class "Default")
      (node (ref "F3") (pin "5") (pinfunction "G1_5") (pintype "bidirectional"))
      (node (ref "IC_MAIN") (pin "42") (pinfunction "U1RX/RF2_42") (pintype "bidirectional"))
    )
    (net (code "84") (name "RF3") (class "Default")
      (node (ref "F3") (pin "3") (pinfunction "G2_3") (pintype "bidirectional"))
      (node (ref "IC_MAIN") (pin "41") (pinfunction "U1TX/RF3_41") (pintype "bidirectional"))
    )
    (net (code "85") (name "RF4") (class "Default")
      (node (ref "IC_MAIN") (pin "39") (pinfunction "U2RX/CN17/RF4_39") (pintype "bidirectional"))
      (node (ref "U$20") (pin "P$2") (pinfunction "2_P$2") (pintype "bidirectional"))
    )
    (net (code "86") (name "RF5") (class "Default")
      (node (ref "IC_MAIN") (pin "40") (pinfunction "U2TX/CN18/RF5_40") (pintype "bidirectional"))
      (node (ref "U$20") (pin "P$5") (pinfunction "5_P$5") (pintype "bidirectional"))
    )
    (net (code "87") (name "RG6") (class "Default")
      (node (ref "IC_MAIN") (pin "6") (pinfunction "SCK2/CN8/RG6_6") (pintype "bidirectional"))
      (node (ref "U$64") (pin "4") (pinfunction "4_4") (pintype "bidirectional"))
    )
    (net (code "88") (name "VPP") (class "Default")
      (node (ref "IC_MAIN") (pin "9") (pinfunction "~{MCLR}_9") (pintype "input"))
      (node (ref "U$1") (pin "1") (pinfunction "1_1") (pintype "bidirectional"))
      (node (ref "U$45") (pin "1") (pinfunction "P$1_1") (pintype "passive"))
    )
    (net (code "89") (name "unconnected-(IC_L_I_D-NC1-Pad1)") (class "Default")
      (node (ref "IC_L_I_D") (pin "1") (pinfunction "NC1_1") (pintype "no_connect"))
    )
    (net (code "90") (name "unconnected-(IC_L_I_D-NC4-Pad4)") (class "Default")
      (node (ref "IC_L_I_D") (pin "4") (pinfunction "NC4_4") (pintype "no_connect"))
    )
    (net (code "91") (name "unconnected-(IC_L_I_D-NC7-Pad7)") (class "Default")
      (node (ref "IC_L_I_D") (pin "7") (pinfunction "NC7_7") (pintype "no_connect"))
    )
    (net (code "92") (name "unconnected-(IC_L_I_U-NC1-Pad1)") (class "Default")
      (node (ref "IC_L_I_U") (pin "1") (pinfunction "NC1_1") (pintype "no_connect"))
    )
    (net (code "93") (name "unconnected-(IC_L_I_U-NC4-Pad4)") (class "Default")
      (node (ref "IC_L_I_U") (pin "4") (pinfunction "NC4_4") (pintype "no_connect"))
    )
    (net (code "94") (name "unconnected-(IC_L_I_U-NC7-Pad7)") (class "Default")
      (node (ref "IC_L_I_U") (pin "7") (pinfunction "NC7_7") (pintype "no_connect"))
    )
    (net (code "95") (name "unconnected-(IC_L_O_D-NC1-Pad1)") (class "Default")
      (node (ref "IC_L_O_D") (pin "1") (pinfunction "NC1_1") (pintype "no_connect"))
    )
    (net (code "96") (name "unconnected-(IC_L_O_D-NC4-Pad4)") (class "Default")
      (node (ref "IC_L_O_D") (pin "4") (pinfunction "NC4_4") (pintype "no_connect"))
    )
    (net (code "97") (name "unconnected-(IC_L_O_D-NC7-Pad7)") (class "Default")
      (node (ref "IC_L_O_D") (pin "7") (pinfunction "NC7_7") (pintype "no_connect"))
    )
    (net (code "98") (name "unconnected-(IC_L_O_U-NC1-Pad1)") (class "Default")
      (node (ref "IC_L_O_U") (pin "1") (pinfunction "NC1_1") (pintype "no_connect"))
    )
    (net (code "99") (name "unconnected-(IC_L_O_U-NC4-Pad4)") (class "Default")
      (node (ref "IC_L_O_U") (pin "4") (pinfunction "NC4_4") (pintype "no_connect"))
    )
    (net (code "100") (name "unconnected-(IC_L_O_U-NC7-Pad7)") (class "Default")
      (node (ref "IC_L_O_U") (pin "7") (pinfunction "NC7_7") (pintype "no_connect"))
    )
    (net (code "101") (name "unconnected-(IC_MAIN-AN10{slash}RB10-Pad29)") (class "Default")
      (node (ref "IC_MAIN") (pin "29") (pinfunction "AN10/RB10_29") (pintype "bidirectional"))
    )
    (net (code "102") (name "unconnected-(IC_MAIN-AN11{slash}RB11-Pad30)") (class "Default")
      (node (ref "IC_MAIN") (pin "30") (pinfunction "AN11/RB11_30") (pintype "bidirectional"))
    )
    (net (code "103") (name "unconnected-(IC_MAIN-AN16{slash}T2CK{slash}T7CK{slash}RC1-Pad4)") (class "Default")
      (node (ref "IC_MAIN") (pin "4") (pinfunction "AN16/T2CK/T7CK/RC1_4") (pintype "bidirectional"))
    )
    (net (code "104") (name "unconnected-(IC_MAIN-AN17{slash}T3CK{slash}T6CK{slash}RC2-Pad5)") (class "Default")
      (node (ref "IC_MAIN") (pin "5") (pinfunction "AN17/T3CK/T6CK/RC2_5") (pintype "bidirectional"))
    )
    (net (code "105") (name "unconnected-(IC_MAIN-C1RX{slash}RF0-Pad72)") (class "Default")
      (node (ref "IC_MAIN") (pin "72") (pinfunction "C1RX/RF0_72") (pintype "bidirectional"))
    )
    (net (code "106") (name "unconnected-(IC_MAIN-C1TX{slash}RF1-Pad73)") (class "Default")
      (node (ref "IC_MAIN") (pin "73") (pinfunction "C1TX/RF1_73") (pintype "bidirectional"))
    )
    (net (code "107") (name "unconnected-(IC_MAIN-IC1{slash}RD8-Pad54)") (class "Default")
      (node (ref "IC_MAIN") (pin "54") (pinfunction "IC1/RD8_54") (pintype "bidirectional"))
    )
    (net (code "108") (name "unconnected-(IC_MAIN-IC4{slash}RD11-Pad57)") (class "Default")
      (node (ref "IC_MAIN") (pin "57") (pinfunction "IC4/RD11_57") (pintype "bidirectional"))
    )
    (net (code "109") (name "unconnected-(IC_MAIN-IC5{slash}RD12-Pad64)") (class "Default")
      (node (ref "IC_MAIN") (pin "64") (pinfunction "IC5/RD12_64") (pintype "bidirectional"))
    )
    (net (code "110") (name "unconnected-(IC_MAIN-RG0-Pad75)") (class "Default")
      (node (ref "IC_MAIN") (pin "75") (pinfunction "RG0_75") (pintype "bidirectional"))
    )
    (net (code "111") (name "unconnected-(IC_MAIN-RG1-Pad74)") (class "Default")
      (node (ref "IC_MAIN") (pin "74") (pinfunction "RG1_74") (pintype "bidirectional"))
    )
    (net (code "112") (name "unconnected-(IC_MAIN-SCK1{slash}INT0{slash}RF6-Pad45)") (class "Default")
      (node (ref "IC_MAIN") (pin "45") (pinfunction "SCK1/INT0/RF6_45") (pintype "bidirectional"))
    )
    (net (code "113") (name "unconnected-(IC_MAIN-SCL1{slash}RG2-Pad47)") (class "Default")
      (node (ref "IC_MAIN") (pin "47") (pinfunction "SCL1/RG2_47") (pintype "bidirectional"))
    )
    (net (code "114") (name "unconnected-(IC_MAIN-SCL2{slash}INT3{slash}RA2-Pad52)") (class "Default")
      (node (ref "IC_MAIN") (pin "52") (pinfunction "SCL2/INT3/RA2_52") (pintype "bidirectional"))
    )
    (net (code "115") (name "unconnected-(IC_MAIN-SDA1{slash}RG3-Pad46)") (class "Default")
      (node (ref "IC_MAIN") (pin "46") (pinfunction "SDA1/RG3_46") (pintype "bidirectional"))
    )
    (net (code "116") (name "unconnected-(IC_MAIN-SDI1{slash}RF7-Pad44)") (class "Default")
      (node (ref "IC_MAIN") (pin "44") (pinfunction "SDI1/RF7_44") (pintype "bidirectional"))
    )
    (net (code "117") (name "unconnected-(IC_MAIN-SDI2{slash}CN9{slash}RG7-Pad7)") (class "Default")
      (node (ref "IC_MAIN") (pin "7") (pinfunction "SDI2/CN9/RG7_7") (pintype "bidirectional"))
    )
    (net (code "118") (name "unconnected-(IC_MAIN-SDO1{slash}RF8-Pad43)") (class "Default")
      (node (ref "IC_MAIN") (pin "43") (pinfunction "SDO1/RF8_43") (pintype "bidirectional"))
    )
    (net (code "119") (name "unconnected-(IC_MAIN-SDO2{slash}CN10{slash}RG8-Pad8)") (class "Default")
      (node (ref "IC_MAIN") (pin "8") (pinfunction "SDO2/CN10/RG8_8") (pintype "bidirectional"))
    )
    (net (code "120") (name "unconnected-(IC_MAIN-TDO{slash}~{FLTB{slash}INT2{slash}RE9}-Pad14)") (class "Default")
      (node (ref "IC_MAIN") (pin "14") (pinfunction "TDO/~{FLTB/INT2/RE9}_14") (pintype "bidirectional"))
    )
    (net (code "121") (name "unconnected-(IC_MAIN-TMS{slash}~{FLTA{slash}INT1{slash}RE8}-Pad13)") (class "Default")
      (node (ref "IC_MAIN") (pin "13") (pinfunction "TMS/~{FLTA/INT1/RE8}_13") (pintype "bidirectional"))
    )
    (net (code "122") (name "unconnected-(IC_MAIN-VREF+{slash}RA10-Pad24)") (class "Default")
      (node (ref "IC_MAIN") (pin "24") (pinfunction "VREF+/RA10_24") (pintype "bidirectional"))
    )
    (net (code "123") (name "unconnected-(IC_MAIN-VREF-{slash}RA9-Pad23)") (class "Default")
      (node (ref "IC_MAIN") (pin "23") (pinfunction "VREF-/RA9_23") (pintype "bidirectional"))
    )
    (net (code "124") (name "unconnected-(IC_MAIN-~{SS2{slash}CN11{slash}RG9}-Pad10)") (class "Default")
      (node (ref "IC_MAIN") (pin "10") (pinfunction "~{SS2/CN11/RG9}_10") (pintype "bidirectional"))
    )
    (net (code "125") (name "unconnected-(IC_MAIN-~{U2CTS{slash}AN8{slash}RB8}-Pad27)") (class "Default")
      (node (ref "IC_MAIN") (pin "27") (pinfunction "~{U2CTS/AN8/RB8}_27") (pintype "bidirectional"))
    )
    (net (code "126") (name "unconnected-(IC_R_I_D-NC1-Pad1)") (class "Default")
      (node (ref "IC_R_I_D") (pin "1") (pinfunction "NC1_1") (pintype "no_connect"))
    )
    (net (code "127") (name "unconnected-(IC_R_I_D-NC4-Pad4)") (class "Default")
      (node (ref "IC_R_I_D") (pin "4") (pinfunction "NC4_4") (pintype "no_connect"))
    )
    (net (code "128") (name "unconnected-(IC_R_I_D-NC7-Pad7)") (class "Default")
      (node (ref "IC_R_I_D") (pin "7") (pinfunction "NC7_7") (pintype "no_connect"))
    )
    (net (code "129") (name "unconnected-(IC_R_I_U-NC1-Pad1)") (class "Default")
      (node (ref "IC_R_I_U") (pin "1") (pinfunction "NC1_1") (pintype "no_connect"))
    )
    (net (code "130") (name "unconnected-(IC_R_I_U-NC4-Pad4)") (class "Default")
      (node (ref "IC_R_I_U") (pin "4") (pinfunction "NC4_4") (pintype "no_connect"))
    )
    (net (code "131") (name "unconnected-(IC_R_I_U-NC7-Pad7)") (class "Default")
      (node (ref "IC_R_I_U") (pin "7") (pinfunction "NC7_7") (pintype "no_connect"))
    )
    (net (code "132") (name "unconnected-(IC_R_O_D-NC1-Pad1)") (class "Default")
      (node (ref "IC_R_O_D") (pin "1") (pinfunction "NC1_1") (pintype "no_connect"))
    )
    (net (code "133") (name "unconnected-(IC_R_O_D-NC4-Pad4)") (class "Default")
      (node (ref "IC_R_O_D") (pin "4") (pinfunction "NC4_4") (pintype "no_connect"))
    )
    (net (code "134") (name "unconnected-(IC_R_O_D-NC7-Pad7)") (class "Default")
      (node (ref "IC_R_O_D") (pin "7") (pinfunction "NC7_7") (pintype "no_connect"))
    )
    (net (code "135") (name "unconnected-(IC_R_O_U-NC1-Pad1)") (class "Default")
      (node (ref "IC_R_O_U") (pin "1") (pinfunction "NC1_1") (pintype "no_connect"))
    )
    (net (code "136") (name "unconnected-(IC_R_O_U-NC4-Pad4)") (class "Default")
      (node (ref "IC_R_O_U") (pin "4") (pinfunction "NC4_4") (pintype "no_connect"))
    )
    (net (code "137") (name "unconnected-(IC_R_O_U-NC7-Pad7)") (class "Default")
      (node (ref "IC_R_O_U") (pin "7") (pinfunction "NC7_7") (pintype "no_connect"))
    )
    (net (code "138") (name "unconnected-(U$64-Pad5)") (class "Default")
      (node (ref "U$64") (pin "5") (pinfunction "5_5") (pintype "bidirectional"))
    )
  )
)
